# power-distribution.net
KiCad netlist of a schematic drawn in EAGLE
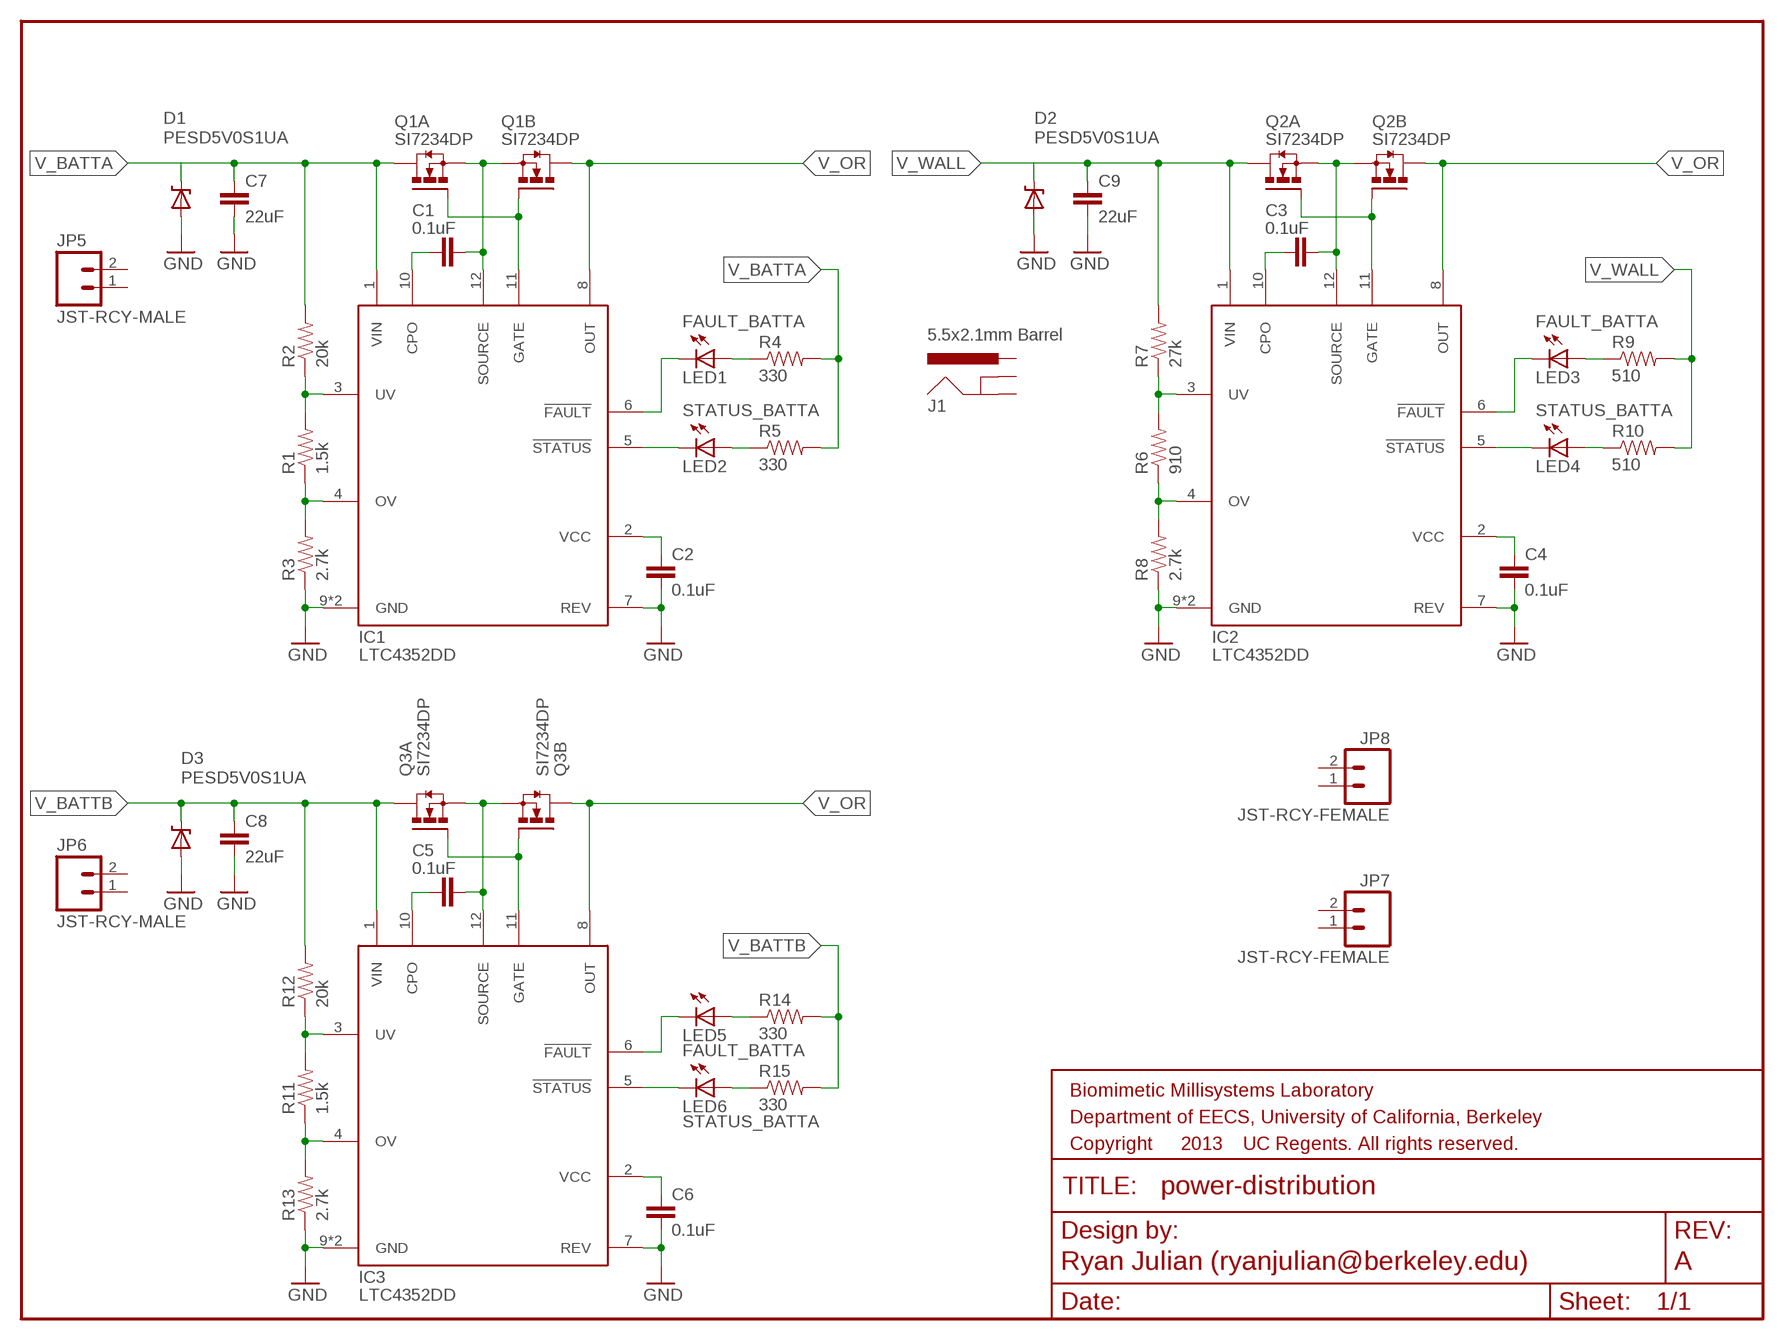
[diagram p0: schematic, sheet 1]

(export (version "E")
  (design (tool "Eeschema 10.0.6"))
  (components
    (comp (ref "C1")
      (value "0.1uF")
      (footprint "eagle-import:0402-CAP")
      (libsource (lib "eagle-import") (part "CAP0402-CAP"))
    )
    (comp (ref "C2")
      (value "0.1uF")
      (footprint "eagle-import:0402-CAP")
      (libsource (lib "eagle-import") (part "CAP0402-CAP"))
    )
    (comp (ref "C3")
      (value "0.1uF")
      (footprint "eagle-import:0402-CAP")
      (libsource (lib "eagle-import") (part "CAP0402-CAP"))
    )
    (comp (ref "C4")
      (value "0.1uF")
      (footprint "eagle-import:0402-CAP")
      (libsource (lib "eagle-import") (part "CAP0402-CAP"))
    )
    (comp (ref "C5")
      (value "0.1uF")
      (footprint "eagle-import:0402-CAP")
      (libsource (lib "eagle-import") (part "CAP0402-CAP"))
    )
    (comp (ref "C6")
      (value "0.1uF")
      (footprint "eagle-import:0402-CAP")
      (libsource (lib "eagle-import") (part "CAP0402-CAP"))
    )
    (comp (ref "C7")
      (value "22uF")
      (footprint "eagle-import:0603-CAP")
      (libsource (lib "eagle-import") (part "CAP0603-CAP"))
    )
    (comp (ref "C8")
      (value "22uF")
      (footprint "eagle-import:0603-CAP")
      (libsource (lib "eagle-import") (part "CAP0603-CAP"))
    )
    (comp (ref "C9")
      (value "22uF")
      (footprint "eagle-import:0603-CAP")
      (libsource (lib "eagle-import") (part "CAP0603-CAP"))
    )
    (comp (ref "D1")
      (value "PESD5V0S1UA")
      (footprint "eagle-import:SOD-323")
      (libsource (lib "eagle-import") (part "PESD5V0S1UA"))
    )
    (comp (ref "D2")
      (value "PESD5V0S1UA")
      (footprint "eagle-import:SOD-323")
      (libsource (lib "eagle-import") (part "PESD5V0S1UA"))
    )
    (comp (ref "D3")
      (value "PESD5V0S1UA")
      (footprint "eagle-import:SOD-323")
      (libsource (lib "eagle-import") (part "PESD5V0S1UA"))
    )
    (comp (ref "IC1")
      (value "LTC4352DD")
      (footprint "eagle-import:DFN-12-3X3-DD")
      (libsource (lib "eagle-import") (part "LTC4352DD"))
    )
    (comp (ref "IC2")
      (value "LTC4352DD")
      (footprint "eagle-import:DFN-12-3X3-DD")
      (libsource (lib "eagle-import") (part "LTC4352DD"))
    )
    (comp (ref "IC3")
      (value "LTC4352DD")
      (footprint "eagle-import:DFN-12-3X3-DD")
      (libsource (lib "eagle-import") (part "LTC4352DD"))
    )
    (comp (ref "J1")
      (value "5.5x2.1mm Barrel")
      (footprint "eagle-import:POWER_JACK_SMD")
      (libsource (lib "eagle-import") (part "POWER_JACKSMD"))
    )
    (comp (ref "JP5")
      (value "JST-RCY-MALE")
      (footprint "eagle-import:JST-RCY-MALE")
      (libsource (lib "eagle-import") (part "JST-RCY-MALE"))
    )
    (comp (ref "JP6")
      (value "JST-RCY-MALE")
      (footprint "eagle-import:JST-RCY-MALE")
      (libsource (lib "eagle-import") (part "JST-RCY-MALE"))
    )
    (comp (ref "JP7")
      (value "JST-RCY-FEMALE")
      (footprint "eagle-import:JST-RCY-FEMALE")
      (libsource (lib "eagle-import") (part "JST-RCY-FEMALE"))
    )
    (comp (ref "JP8")
      (value "JST-RCY-FEMALE")
      (footprint "eagle-import:JST-RCY-FEMALE")
      (libsource (lib "eagle-import") (part "JST-RCY-FEMALE"))
    )
    (comp (ref "LED1")
      (value "FAULT_BATTA")
      (footprint "eagle-import:LED-0603")
      (libsource (lib "eagle-import") (part "LED0603"))
    )
    (comp (ref "LED2")
      (value "STATUS_BATTA")
      (footprint "eagle-import:LED-0603")
      (libsource (lib "eagle-import") (part "LED0603"))
    )
    (comp (ref "LED3")
      (value "FAULT_BATTA")
      (footprint "eagle-import:LED-0603")
      (libsource (lib "eagle-import") (part "LED0603"))
    )
    (comp (ref "LED4")
      (value "STATUS_BATTA")
      (footprint "eagle-import:LED-0603")
      (libsource (lib "eagle-import") (part "LED0603"))
    )
    (comp (ref "LED5")
      (value "FAULT_BATTA")
      (footprint "eagle-import:LED-0603")
      (libsource (lib "eagle-import") (part "LED0603"))
    )
    (comp (ref "LED6")
      (value "STATUS_BATTA")
      (footprint "eagle-import:LED-0603")
      (libsource (lib "eagle-import") (part "LED0603"))
    )
    (comp (ref "Q1")
      (value "SI7234DP")
      (footprint "eagle-import:POWERPAK-SO-8-DUAL")
      (libsource (lib "eagle-import") (part "SI7234DP"))
    )
    (comp (ref "Q2")
      (value "SI7234DP")
      (footprint "eagle-import:POWERPAK-SO-8-DUAL")
      (libsource (lib "eagle-import") (part "SI7234DP"))
    )
    (comp (ref "Q3")
      (value "SI7234DP")
      (footprint "eagle-import:POWERPAK-SO-8-DUAL")
      (libsource (lib "eagle-import") (part "SI7234DP"))
    )
    (comp (ref "R1")
      (value "1.5k")
      (footprint "eagle-import:0402-RES")
      (libsource (lib "eagle-import") (part "RESISTOR0402-RES"))
    )
    (comp (ref "R2")
      (value "20k")
      (footprint "eagle-import:0402-RES")
      (libsource (lib "eagle-import") (part "RESISTOR0402-RES"))
    )
    (comp (ref "R3")
      (value "2.7k")
      (footprint "eagle-import:0402-RES")
      (libsource (lib "eagle-import") (part "RESISTOR0402-RES"))
    )
    (comp (ref "R4")
      (value "330")
      (footprint "eagle-import:0402-RES")
      (libsource (lib "eagle-import") (part "RESISTOR0402-RES"))
    )
    (comp (ref "R5")
      (value "330")
      (footprint "eagle-import:0402-RES")
      (libsource (lib "eagle-import") (part "RESISTOR0402-RES"))
    )
    (comp (ref "R6")
      (value "910")
      (footprint "eagle-import:0402-RES")
      (libsource (lib "eagle-import") (part "RESISTOR0402-RES"))
    )
    (comp (ref "R7")
      (value "27k")
      (footprint "eagle-import:0402-RES")
      (libsource (lib "eagle-import") (part "RESISTOR0402-RES"))
    )
    (comp (ref "R8")
      (value "2.7k")
      (footprint "eagle-import:0402-RES")
      (libsource (lib "eagle-import") (part "RESISTOR0402-RES"))
    )
    (comp (ref "R9")
      (value "510")
      (footprint "eagle-import:0402-RES")
      (libsource (lib "eagle-import") (part "RESISTOR0402-RES"))
    )
    (comp (ref "R10")
      (value "510")
      (footprint "eagle-import:0402-RES")
      (libsource (lib "eagle-import") (part "RESISTOR0402-RES"))
    )
    (comp (ref "R11")
      (value "1.5k")
      (footprint "eagle-import:0402-RES")
      (libsource (lib "eagle-import") (part "RESISTOR0402-RES"))
    )
    (comp (ref "R12")
      (value "20k")
      (footprint "eagle-import:0402-RES")
      (libsource (lib "eagle-import") (part "RESISTOR0402-RES"))
    )
    (comp (ref "R13")
      (value "2.7k")
      (footprint "eagle-import:0402-RES")
      (libsource (lib "eagle-import") (part "RESISTOR0402-RES"))
    )
    (comp (ref "R14")
      (value "330")
      (footprint "eagle-import:0402-RES")
      (libsource (lib "eagle-import") (part "RESISTOR0402-RES"))
    )
    (comp (ref "R15")
      (value "330")
      (footprint "eagle-import:0402-RES")
      (libsource (lib "eagle-import") (part "RESISTOR0402-RES"))
    )
  )
  (nets
    (net (code "1") (name "GND") (class "Default")
      (node (ref "C2") (pin "2") (pinfunction "2_2") (pintype "passive"))
      (node (ref "C4") (pin "2") (pinfunction "2_2") (pintype "passive"))
      (node (ref "C6") (pin "2") (pinfunction "2_2") (pintype "passive"))
      (node (ref "C7") (pin "2") (pinfunction "2_2") (pintype "passive"))
      (node (ref "C8") (pin "2") (pinfunction "2_2") (pintype "passive"))
      (node (ref "C9") (pin "2") (pinfunction "2_2") (pintype "passive"))
      (node (ref "D1") (pin "2") (pinfunction "A_2") (pintype "passive"))
      (node (ref "D2") (pin "2") (pinfunction "A_2") (pintype "passive"))
      (node (ref "D3") (pin "2") (pinfunction "A_2") (pintype "passive"))
      (node (ref "IC1") (pin "7") (pinfunction "REV_7") (pintype "bidirectional"))
      (node (ref "IC1") (pin "9") (pinfunction "GND_9") (pintype "bidirectional"))
      (node (ref "IC1") (pin "PAD") (pinfunction "GND_PAD") (pintype "bidirectional"))
      (node (ref "IC2") (pin "7") (pinfunction "REV_7") (pintype "bidirectional"))
      (node (ref "IC2") (pin "9") (pinfunction "GND_9") (pintype "bidirectional"))
      (node (ref "IC2") (pin "PAD") (pinfunction "GND_PAD") (pintype "bidirectional"))
      (node (ref "IC3") (pin "7") (pinfunction "REV_7") (pintype "bidirectional"))
      (node (ref "IC3") (pin "9") (pinfunction "GND_9") (pintype "bidirectional"))
      (node (ref "IC3") (pin "PAD") (pinfunction "GND_PAD") (pintype "bidirectional"))
      (node (ref "R13") (pin "1") (pinfunction "1_1") (pintype "passive"))
      (node (ref "R3") (pin "1") (pinfunction "1_1") (pintype "passive"))
      (node (ref "R8") (pin "1") (pinfunction "1_1") (pintype "passive"))
    )
    (net (code "2") (name "Net-(IC1-CPO)") (class "Default")
      (node (ref "C1") (pin "1") (pinfunction "1_1") (pintype "passive"))
      (node (ref "IC1") (pin "10") (pinfunction "CPO_10") (pintype "bidirectional"))
    )
    (net (code "3") (name "Net-(IC1-GATE)") (class "Default")
      (node (ref "IC1") (pin "11") (pinfunction "GATE_11") (pintype "bidirectional"))
      (node (ref "Q1") (pin "2") (pinfunction "G_2") (pintype "passive"))
      (node (ref "Q1") (pin "4") (pinfunction "G_4") (pintype "passive"))
    )
    (net (code "4") (name "Net-(IC1-OV)") (class "Default")
      (node (ref "IC1") (pin "4") (pinfunction "OV_4") (pintype "bidirectional"))
      (node (ref "R1") (pin "1") (pinfunction "1_1") (pintype "passive"))
      (node (ref "R3") (pin "2") (pinfunction "2_2") (pintype "passive"))
    )
    (net (code "5") (name "Net-(IC1-SOURCE)") (class "Default")
      (node (ref "C1") (pin "2") (pinfunction "2_2") (pintype "passive"))
      (node (ref "IC1") (pin "12") (pinfunction "SOURCE_12") (pintype "bidirectional"))
      (node (ref "Q1") (pin "1") (pinfunction "S_1") (pintype "passive"))
      (node (ref "Q1") (pin "3") (pinfunction "S_3") (pintype "passive"))
    )
    (net (code "6") (name "Net-(IC1-UV)") (class "Default")
      (node (ref "IC1") (pin "3") (pinfunction "UV_3") (pintype "bidirectional"))
      (node (ref "R1") (pin "2") (pinfunction "2_2") (pintype "passive"))
      (node (ref "R2") (pin "1") (pinfunction "1_1") (pintype "passive"))
    )
    (net (code "7") (name "Net-(IC1-VCC)") (class "Default")
      (node (ref "C2") (pin "1") (pinfunction "1_1") (pintype "passive"))
      (node (ref "IC1") (pin "2") (pinfunction "VCC_2") (pintype "bidirectional"))
    )
    (net (code "8") (name "Net-(IC1-~{FAULT})") (class "Default")
      (node (ref "IC1") (pin "6") (pinfunction "~{FAULT}_6") (pintype "bidirectional"))
      (node (ref "LED1") (pin "C") (pinfunction "C_C") (pintype "passive"))
    )
    (net (code "9") (name "Net-(IC1-~{STATUS})") (class "Default")
      (node (ref "IC1") (pin "5") (pinfunction "~{STATUS}_5") (pintype "bidirectional"))
      (node (ref "LED2") (pin "C") (pinfunction "C_C") (pintype "passive"))
    )
    (net (code "10") (name "Net-(IC2-CPO)") (class "Default")
      (node (ref "C3") (pin "1") (pinfunction "1_1") (pintype "passive"))
      (node (ref "IC2") (pin "10") (pinfunction "CPO_10") (pintype "bidirectional"))
    )
    (net (code "11") (name "Net-(IC2-GATE)") (class "Default")
      (node (ref "IC2") (pin "11") (pinfunction "GATE_11") (pintype "bidirectional"))
      (node (ref "Q2") (pin "2") (pinfunction "G_2") (pintype "passive"))
      (node (ref "Q2") (pin "4") (pinfunction "G_4") (pintype "passive"))
    )
    (net (code "12") (name "Net-(IC2-OV)") (class "Default")
      (node (ref "IC2") (pin "4") (pinfunction "OV_4") (pintype "bidirectional"))
      (node (ref "R6") (pin "1") (pinfunction "1_1") (pintype "passive"))
      (node (ref "R8") (pin "2") (pinfunction "2_2") (pintype "passive"))
    )
    (net (code "13") (name "Net-(IC2-SOURCE)") (class "Default")
      (node (ref "C3") (pin "2") (pinfunction "2_2") (pintype "passive"))
      (node (ref "IC2") (pin "12") (pinfunction "SOURCE_12") (pintype "bidirectional"))
      (node (ref "Q2") (pin "1") (pinfunction "S_1") (pintype "passive"))
      (node (ref "Q2") (pin "3") (pinfunction "S_3") (pintype "passive"))
    )
    (net (code "14") (name "Net-(IC2-UV)") (class "Default")
      (node (ref "IC2") (pin "3") (pinfunction "UV_3") (pintype "bidirectional"))
      (node (ref "R6") (pin "2") (pinfunction "2_2") (pintype "passive"))
      (node (ref "R7") (pin "1") (pinfunction "1_1") (pintype "passive"))
    )
    (net (code "15") (name "Net-(IC2-VCC)") (class "Default")
      (node (ref "C4") (pin "1") (pinfunction "1_1") (pintype "passive"))
      (node (ref "IC2") (pin "2") (pinfunction "VCC_2") (pintype "bidirectional"))
    )
    (net (code "16") (name "Net-(IC2-~{FAULT})") (class "Default")
      (node (ref "IC2") (pin "6") (pinfunction "~{FAULT}_6") (pintype "bidirectional"))
      (node (ref "LED3") (pin "C") (pinfunction "C_C") (pintype "passive"))
    )
    (net (code "17") (name "Net-(IC2-~{STATUS})") (class "Default")
      (node (ref "IC2") (pin "5") (pinfunction "~{STATUS}_5") (pintype "bidirectional"))
      (node (ref "LED4") (pin "C") (pinfunction "C_C") (pintype "passive"))
    )
    (net (code "18") (name "Net-(IC3-CPO)") (class "Default")
      (node (ref "C5") (pin "1") (pinfunction "1_1") (pintype "passive"))
      (node (ref "IC3") (pin "10") (pinfunction "CPO_10") (pintype "bidirectional"))
    )
    (net (code "19") (name "Net-(IC3-GATE)") (class "Default")
      (node (ref "IC3") (pin "11") (pinfunction "GATE_11") (pintype "bidirectional"))
      (node (ref "Q3") (pin "2") (pinfunction "G_2") (pintype "passive"))
      (node (ref "Q3") (pin "4") (pinfunction "G_4") (pintype "passive"))
    )
    (net (code "20") (name "Net-(IC3-OV)") (class "Default")
      (node (ref "IC3") (pin "4") (pinfunction "OV_4") (pintype "bidirectional"))
      (node (ref "R11") (pin "1") (pinfunction "1_1") (pintype "passive"))
      (node (ref "R13") (pin "2") (pinfunction "2_2") (pintype "passive"))
    )
    (net (code "21") (name "Net-(IC3-SOURCE)") (class "Default")
      (node (ref "C5") (pin "2") (pinfunction "2_2") (pintype "passive"))
      (node (ref "IC3") (pin "12") (pinfunction "SOURCE_12") (pintype "bidirectional"))
      (node (ref "Q3") (pin "1") (pinfunction "S_1") (pintype "passive"))
      (node (ref "Q3") (pin "3") (pinfunction "S_3") (pintype "passive"))
    )
    (net (code "22") (name "Net-(IC3-UV)") (class "Default")
      (node (ref "IC3") (pin "3") (pinfunction "UV_3") (pintype "bidirectional"))
      (node (ref "R11") (pin "2") (pinfunction "2_2") (pintype "passive"))
      (node (ref "R12") (pin "1") (pinfunction "1_1") (pintype "passive"))
    )
    (net (code "23") (name "Net-(IC3-VCC)") (class "Default")
      (node (ref "C6") (pin "1") (pinfunction "1_1") (pintype "passive"))
      (node (ref "IC3") (pin "2") (pinfunction "VCC_2") (pintype "bidirectional"))
    )
    (net (code "24") (name "Net-(IC3-~{FAULT})") (class "Default")
      (node (ref "IC3") (pin "6") (pinfunction "~{FAULT}_6") (pintype "bidirectional"))
      (node (ref "LED5") (pin "C") (pinfunction "C_C") (pintype "passive"))
    )
    (net (code "25") (name "Net-(IC3-~{STATUS})") (class "Default")
      (node (ref "IC3") (pin "5") (pinfunction "~{STATUS}_5") (pintype "bidirectional"))
      (node (ref "LED6") (pin "C") (pinfunction "C_C") (pintype "passive"))
    )
    (net (code "26") (name "Net-(LED1-PadA)") (class "Default")
      (node (ref "LED1") (pin "A") (pinfunction "A_A") (pintype "passive"))
      (node (ref "R4") (pin "1") (pinfunction "1_1") (pintype "passive"))
    )
    (net (code "27") (name "Net-(LED2-PadA)") (class "Default")
      (node (ref "LED2") (pin "A") (pinfunction "A_A") (pintype "passive"))
      (node (ref "R5") (pin "1") (pinfunction "1_1") (pintype "passive"))
    )
    (net (code "28") (name "Net-(LED3-PadA)") (class "Default")
      (node (ref "LED3") (pin "A") (pinfunction "A_A") (pintype "passive"))
      (node (ref "R9") (pin "1") (pinfunction "1_1") (pintype "passive"))
    )
    (net (code "29") (name "Net-(LED4-PadA)") (class "Default")
      (node (ref "LED4") (pin "A") (pinfunction "A_A") (pintype "passive"))
      (node (ref "R10") (pin "1") (pinfunction "1_1") (pintype "passive"))
    )
    (net (code "30") (name "Net-(LED5-PadA)") (class "Default")
      (node (ref "LED5") (pin "A") (pinfunction "A_A") (pintype "passive"))
      (node (ref "R14") (pin "1") (pinfunction "1_1") (pintype "passive"))
    )
    (net (code "31") (name "Net-(LED6-PadA)") (class "Default")
      (node (ref "LED6") (pin "A") (pinfunction "A_A") (pintype "passive"))
      (node (ref "R15") (pin "1") (pinfunction "1_1") (pintype "passive"))
    )
    (net (code "32") (name "V_BATTA") (class "Default")
      (node (ref "C7") (pin "1") (pinfunction "1_1") (pintype "passive"))
      (node (ref "D1") (pin "1") (pinfunction "C_1") (pintype "passive"))
      (node (ref "IC1") (pin "1") (pinfunction "VIN_1") (pintype "bidirectional"))
      (node (ref "Q1") (pin "7+8") (pinfunction "D_7+8") (pintype "passive"))
      (node (ref "R2") (pin "2") (pinfunction "2_2") (pintype "passive"))
      (node (ref "R4") (pin "2") (pinfunction "2_2") (pintype "passive"))
      (node (ref "R5") (pin "2") (pinfunction "2_2") (pintype "passive"))
    )
    (net (code "33") (name "V_BATTB") (class "Default")
      (node (ref "C8") (pin "1") (pinfunction "1_1") (pintype "passive"))
      (node (ref "D3") (pin "1") (pinfunction "C_1") (pintype "passive"))
      (node (ref "IC3") (pin "1") (pinfunction "VIN_1") (pintype "bidirectional"))
      (node (ref "Q3") (pin "7+8") (pinfunction "D_7+8") (pintype "passive"))
      (node (ref "R12") (pin "2") (pinfunction "2_2") (pintype "passive"))
      (node (ref "R14") (pin "2") (pinfunction "2_2") (pintype "passive"))
      (node (ref "R15") (pin "2") (pinfunction "2_2") (pintype "passive"))
    )
    (net (code "34") (name "V_OR") (class "Default")
      (node (ref "IC1") (pin "8") (pinfunction "OUT_8") (pintype "bidirectional"))
      (node (ref "IC2") (pin "8") (pinfunction "OUT_8") (pintype "bidirectional"))
      (node (ref "IC3") (pin "8") (pinfunction "OUT_8") (pintype "bidirectional"))
      (node (ref "Q1") (pin "5+6") (pinfunction "D_5+6") (pintype "passive"))
      (node (ref "Q2") (pin "5+6") (pinfunction "D_5+6") (pintype "passive"))
      (node (ref "Q3") (pin "5+6") (pinfunction "D_5+6") (pintype "passive"))
    )
    (net (code "35") (name "V_WALL") (class "Default")
      (node (ref "C9") (pin "1") (pinfunction "1_1") (pintype "passive"))
      (node (ref "D2") (pin "1") (pinfunction "C_1") (pintype "passive"))
      (node (ref "IC2") (pin "1") (pinfunction "VIN_1") (pintype "bidirectional"))
      (node (ref "Q2") (pin "7+8") (pinfunction "D_7+8") (pintype "passive"))
      (node (ref "R10") (pin "2") (pinfunction "2_2") (pintype "passive"))
      (node (ref "R7") (pin "2") (pinfunction "2_2") (pintype "passive"))
      (node (ref "R9") (pin "2") (pinfunction "2_2") (pintype "passive"))
    )
    (net (code "36") (name "unconnected-(J1-GND-PadP$4)") (class "Default")
      (node (ref "J1") (pin "P$4") (pinfunction "GND_P$4") (pintype "bidirectional"))
    )
    (net (code "37") (name "unconnected-(J1-GNDBREAK-PadGND)") (class "Default")
      (node (ref "J1") (pin "GND") (pinfunction "GNDBREAK_GND") (pintype "bidirectional"))
    )
    (net (code "38") (name "unconnected-(J1-PWR-PadVIN0)") (class "Default")
      (node (ref "J1") (pin "VIN0") (pinfunction "PWR_VIN0") (pintype "bidirectional"))
    )
    (net (code "39") (name "unconnected-(JP5-Pad1)") (class "Default")
      (node (ref "JP5") (pin "1") (pinfunction "1_1") (pintype "passive"))
    )
    (net (code "40") (name "unconnected-(JP5-Pad2)") (class "Default")
      (node (ref "JP5") (pin "2") (pinfunction "2_2") (pintype "passive"))
    )
    (net (code "41") (name "unconnected-(JP6-Pad1)") (class "Default")
      (node (ref "JP6") (pin "1") (pinfunction "1_1") (pintype "passive"))
    )
    (net (code "42") (name "unconnected-(JP6-Pad2)") (class "Default")
      (node (ref "JP6") (pin "2") (pinfunction "2_2") (pintype "passive"))
    )
    (net (code "43") (name "unconnected-(JP7-Pad1)") (class "Default")
      (node (ref "JP7") (pin "1") (pinfunction "1_1") (pintype "passive"))
    )
    (net (code "44") (name "unconnected-(JP7-Pad2)") (class "Default")
      (node (ref "JP7") (pin "2") (pinfunction "2_2") (pintype "passive"))
    )
    (net (code "45") (name "unconnected-(JP8-Pad1)") (class "Default")
      (node (ref "JP8") (pin "1") (pinfunction "1_1") (pintype "passive"))
    )
    (net (code "46") (name "unconnected-(JP8-Pad2)") (class "Default")
      (node (ref "JP8") (pin "2") (pinfunction "2_2") (pintype "passive"))
    )
  )
)
